# GeigerCounter.net
KiCad netlist of a schematic drawn in EAGLE
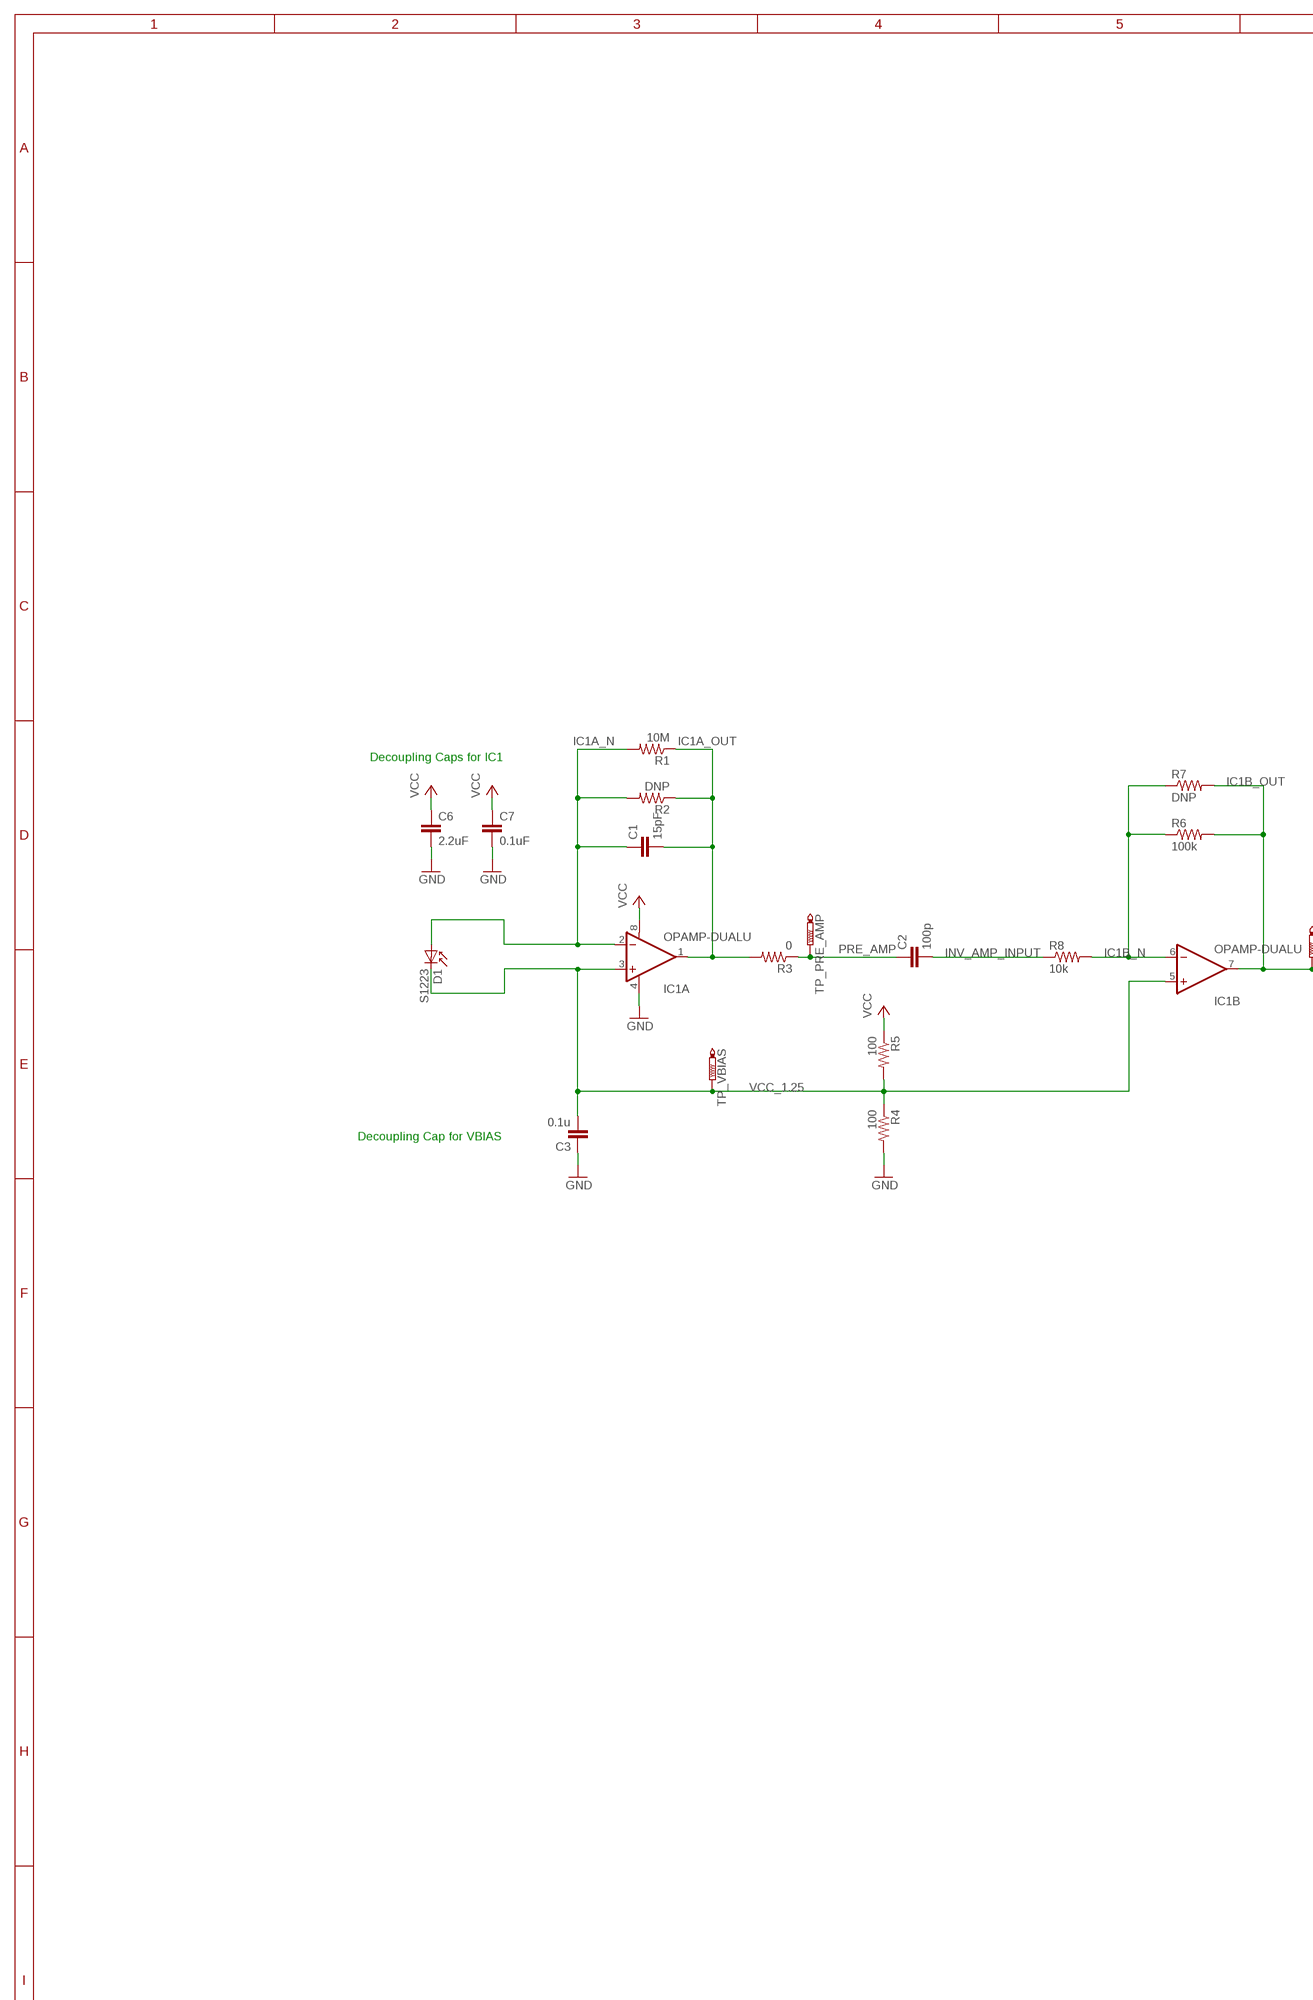
[diagram p0: schematic, sheet 1, part 1 of 2]
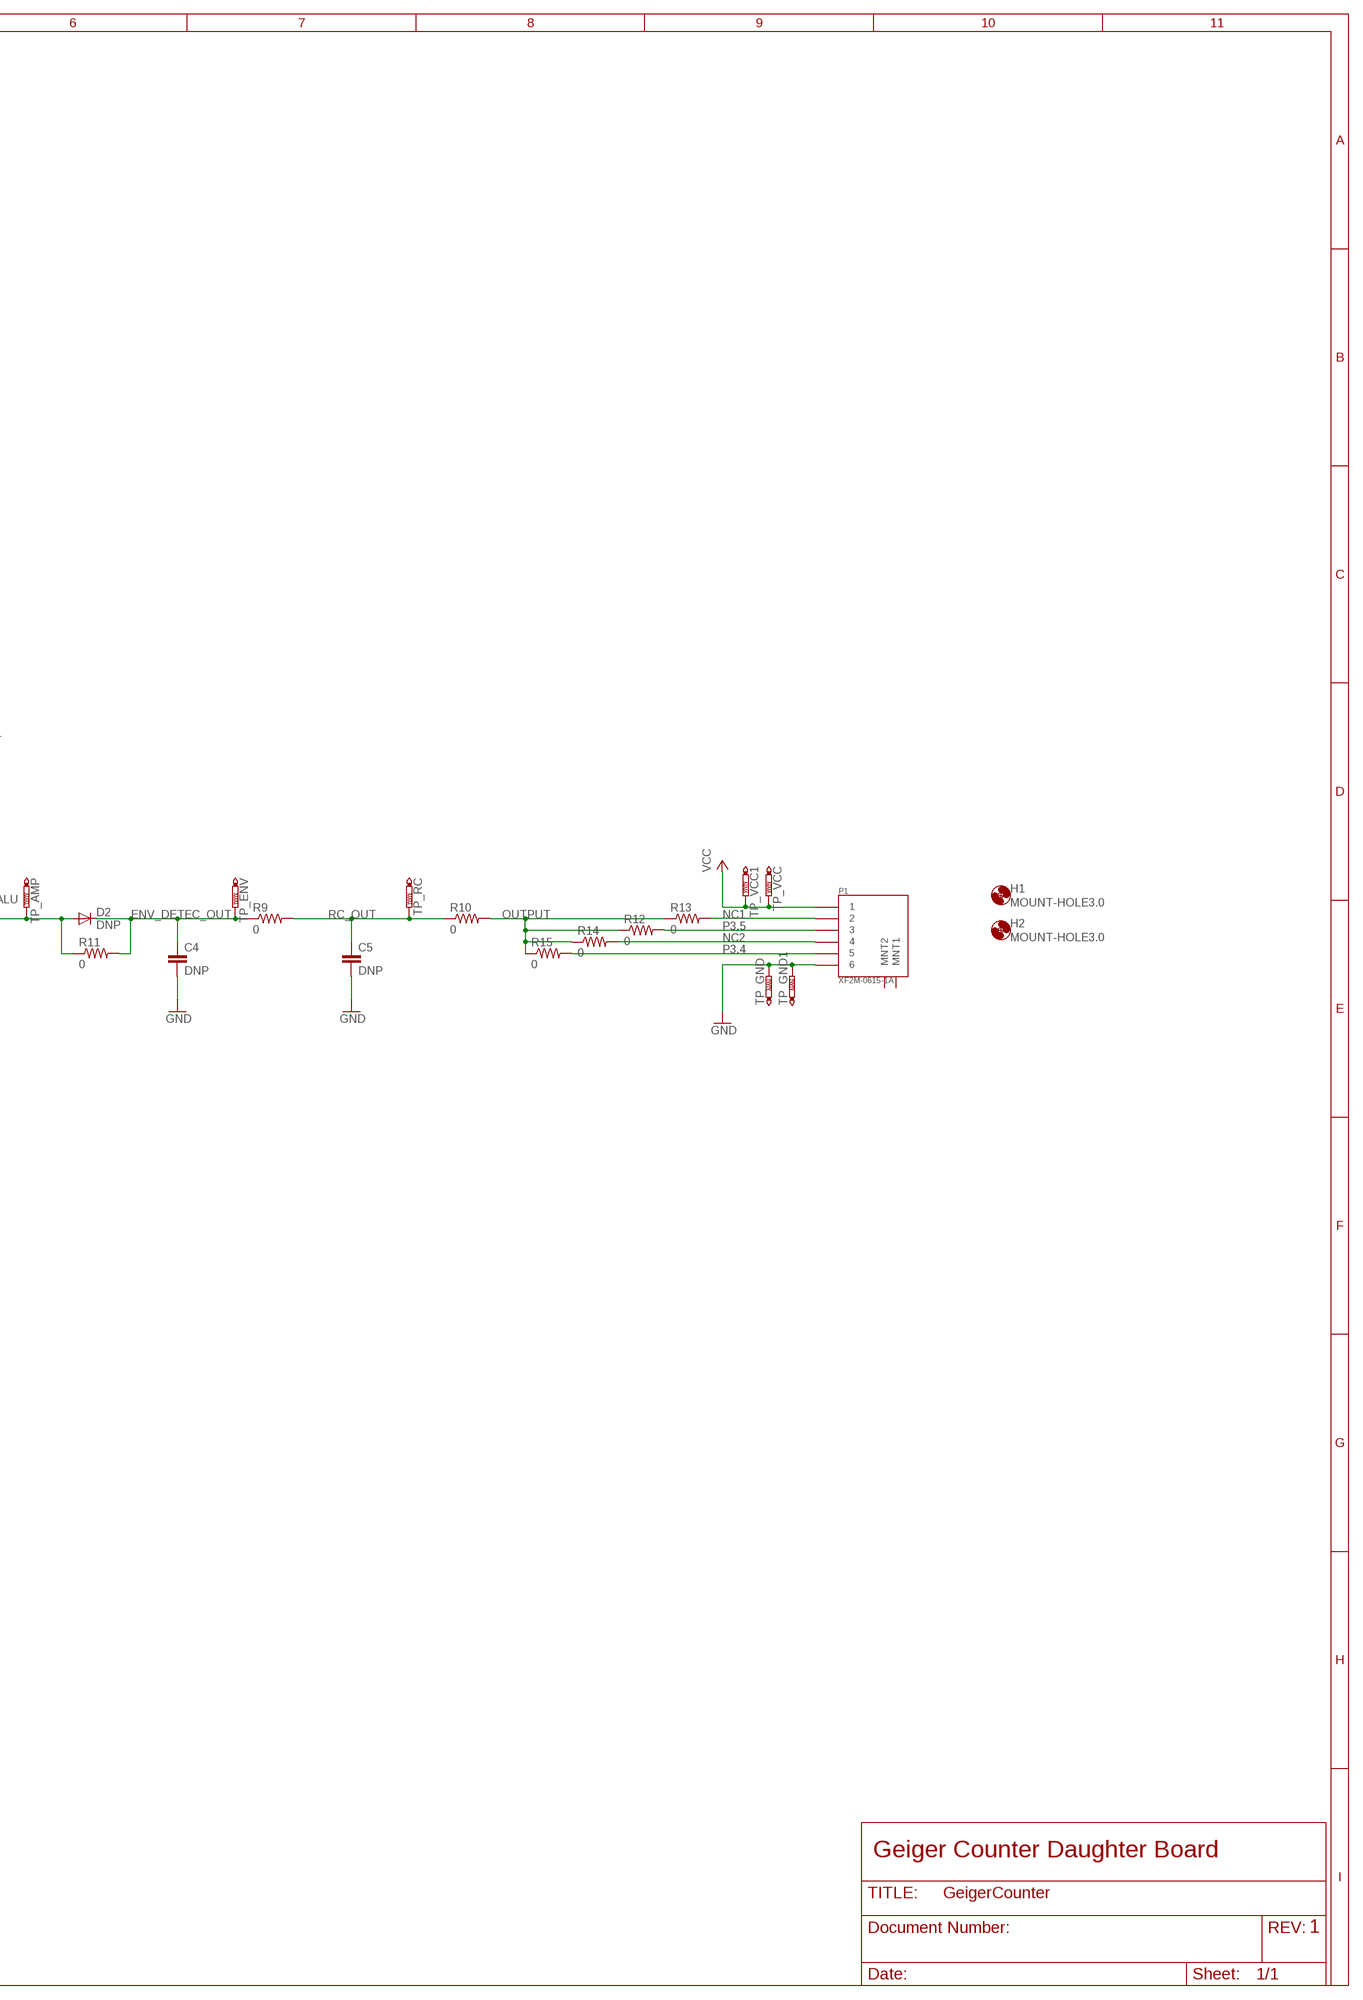
[diagram p1: schematic, sheet 1, part 2 of 2]

(export (version "E")
  (design (tool "Eeschema 10.0.6"))
  (components
    (comp (ref "C1")
      (value "15pF")
      (footprint "eagle-import:0603-CAP")
      (libsource (lib "eagle-import") (part "CAP0603-CAP"))
    )
    (comp (ref "C2")
      (value "100p")
      (footprint "eagle-import:0603-CAP")
      (libsource (lib "eagle-import") (part "CAP0603-CAP"))
    )
    (comp (ref "C3")
      (value "0.1u")
      (footprint "eagle-import:0603-CAP")
      (libsource (lib "eagle-import") (part "CAP0603-CAP"))
    )
    (comp (ref "C4")
      (value "DNP")
      (footprint "eagle-import:0603-CAP")
      (libsource (lib "eagle-import") (part "CAP0603-CAP"))
    )
    (comp (ref "C5")
      (value "DNP")
      (footprint "eagle-import:0603-CAP")
      (libsource (lib "eagle-import") (part "CAP0603-CAP"))
    )
    (comp (ref "C6")
      (value "2.2uF")
      (footprint "eagle-import:0603-CAP")
      (libsource (lib "eagle-import") (part "CAP0603-CAP"))
    )
    (comp (ref "C7")
      (value "0.1uF")
      (footprint "eagle-import:0603-CAP")
      (libsource (lib "eagle-import") (part "CAP0603-CAP"))
    )
    (comp (ref "D1")
      (value "S1223")
      (footprint "eagle-import:DIODE-1N4001")
      (libsource (lib "eagle-import") (part "S1223"))
    )
    (comp (ref "D2")
      (value "DNP")
      (footprint "eagle-import:SOT23-3")
      (libsource (lib "eagle-import") (part "DIODESOT23"))
    )
    (comp (ref "H1")
      (value "MOUNT-HOLE3.0")
      (footprint "eagle-import:3,0")
      (libsource (lib "eagle-import") (part "MOUNT-HOLE3.0"))
    )
    (comp (ref "H2")
      (value "MOUNT-HOLE3.0")
      (footprint "eagle-import:3,0")
      (libsource (lib "eagle-import") (part "MOUNT-HOLE3.0"))
    )
    (comp (ref "IC1")
      (value "OPAMP-DUALU")
      (footprint "eagle-import:SO08")
      (libsource (lib "eagle-import") (part "OPAMP-DUALU"))
    )
    (comp (ref "P1")
      (value "XF2M-0615-1A")
      (footprint "eagle-import:XF2M-0615-1A")
      (libsource (lib "eagle-import") (part "XF2M-0615-1A"))
    )
    (comp (ref "R1")
      (value "10M")
      (footprint "eagle-import:0603-RES")
      (libsource (lib "eagle-import") (part "RESISTOR0603-RES"))
    )
    (comp (ref "R2")
      (value "DNP")
      (footprint "eagle-import:0603-RES")
      (libsource (lib "eagle-import") (part "RESISTOR0603-RES"))
    )
    (comp (ref "R3")
      (value "0")
      (footprint "eagle-import:0603-RES")
      (libsource (lib "eagle-import") (part "RESISTOR0603-RES"))
    )
    (comp (ref "R4")
      (value "100")
      (footprint "eagle-import:0603-RES")
      (libsource (lib "eagle-import") (part "RESISTOR0603-RES"))
    )
    (comp (ref "R5")
      (value "100")
      (footprint "eagle-import:0603-RES")
      (libsource (lib "eagle-import") (part "RESISTOR0603-RES"))
    )
    (comp (ref "R6")
      (value "100k")
      (footprint "eagle-import:0603-RES")
      (libsource (lib "eagle-import") (part "RESISTOR0603-RES"))
    )
    (comp (ref "R7")
      (value "DNP")
      (footprint "eagle-import:0603-RES")
      (libsource (lib "eagle-import") (part "RESISTOR0603-RES"))
    )
    (comp (ref "R8")
      (value "10k")
      (footprint "eagle-import:0603-RES")
      (libsource (lib "eagle-import") (part "RESISTOR0603-RES"))
    )
    (comp (ref "R9")
      (value "0")
      (footprint "eagle-import:0603-RES")
      (libsource (lib "eagle-import") (part "RESISTOR0603-RES"))
    )
    (comp (ref "R10")
      (value "0")
      (footprint "eagle-import:0603-RES")
      (libsource (lib "eagle-import") (part "RESISTOR0603-RES"))
    )
    (comp (ref "R11")
      (value "0")
      (footprint "eagle-import:0603-RES")
      (libsource (lib "eagle-import") (part "RESISTOR0603-RES"))
    )
    (comp (ref "R12")
      (value "0")
      (footprint "eagle-import:0603-RES")
      (libsource (lib "eagle-import") (part "RESISTOR0603-RES"))
    )
    (comp (ref "R13")
      (value "0")
      (footprint "eagle-import:0603-RES")
      (libsource (lib "eagle-import") (part "RESISTOR0603-RES"))
    )
    (comp (ref "R14")
      (value "0")
      (footprint "eagle-import:0603-RES")
      (libsource (lib "eagle-import") (part "RESISTOR0603-RES"))
    )
    (comp (ref "R15")
      (value "0")
      (footprint "eagle-import:0603-RES")
      (libsource (lib "eagle-import") (part "RESISTOR0603-RES"))
    )
    (comp (ref "TP_AMP")
      (value "PTR1PAD1-20")
      (footprint "eagle-import:P1-20")
      (libsource (lib "eagle-import") (part "PTR1PAD1-20"))
    )
    (comp (ref "TP_ENV")
      (value "PTR1PAD1-20")
      (footprint "eagle-import:P1-20")
      (libsource (lib "eagle-import") (part "PTR1PAD1-20"))
    )
    (comp (ref "TP_GND")
      (value "PTR1PAD1-20")
      (footprint "eagle-import:P1-20")
      (libsource (lib "eagle-import") (part "PTR1PAD1-20"))
    )
    (comp (ref "TP_GND1")
      (value "PTR1PAD1-20")
      (footprint "eagle-import:P1-20")
      (libsource (lib "eagle-import") (part "PTR1PAD1-20"))
    )
    (comp (ref "TP_PRE_AMP")
      (value "PTR1PAD1-20")
      (footprint "eagle-import:P1-20")
      (libsource (lib "eagle-import") (part "PTR1PAD1-20"))
    )
    (comp (ref "TP_RC")
      (value "PTR1PAD1-20")
      (footprint "eagle-import:P1-20")
      (libsource (lib "eagle-import") (part "PTR1PAD1-20"))
    )
    (comp (ref "TP_VBIAS")
      (value "PTR1PAD1-20")
      (footprint "eagle-import:P1-20")
      (libsource (lib "eagle-import") (part "PTR1PAD1-20"))
    )
    (comp (ref "TP_VCC")
      (value "PTR1PAD1-20")
      (footprint "eagle-import:P1-20")
      (libsource (lib "eagle-import") (part "PTR1PAD1-20"))
    )
    (comp (ref "TP_VCC1")
      (value "PTR1PAD1-20")
      (footprint "eagle-import:P1-20")
      (libsource (lib "eagle-import") (part "PTR1PAD1-20"))
    )
  )
  (nets
    (net (code "1") (name "/ENV_DETEC_OUT") (class "Default")
      (node (ref "C4") (pin "1") (pinfunction "1_1") (pintype "passive"))
      (node (ref "D2") (pin "3") (pinfunction "C_3") (pintype "passive"))
      (node (ref "R11") (pin "2") (pinfunction "2_2") (pintype "passive"))
      (node (ref "R9") (pin "1") (pinfunction "1_1") (pintype "passive"))
      (node (ref "TP_ENV") (pin "TP") (pinfunction "TP_TP") (pintype "input"))
    )
    (net (code "2") (name "/IC1A_N") (class "Default")
      (node (ref "C1") (pin "1") (pinfunction "1_1") (pintype "passive"))
      (node (ref "D1") (pin "A") (pinfunction "A_A") (pintype "passive"))
      (node (ref "IC1") (pin "2") (pinfunction "-IN_2") (pintype "input"))
      (node (ref "R1") (pin "2") (pinfunction "2_2") (pintype "passive"))
      (node (ref "R2") (pin "2") (pinfunction "2_2") (pintype "passive"))
    )
    (net (code "3") (name "/IC1A_OUT") (class "Default")
      (node (ref "C1") (pin "2") (pinfunction "2_2") (pintype "passive"))
      (node (ref "IC1") (pin "1") (pinfunction "OUT_1") (pintype "output"))
      (node (ref "R1") (pin "1") (pinfunction "1_1") (pintype "passive"))
      (node (ref "R2") (pin "1") (pinfunction "1_1") (pintype "passive"))
      (node (ref "R3") (pin "2") (pinfunction "2_2") (pintype "passive"))
    )
    (net (code "4") (name "/IC1B_N") (class "Default")
      (node (ref "IC1") (pin "6") (pinfunction "-IN_6") (pintype "input"))
      (node (ref "R6") (pin "1") (pinfunction "1_1") (pintype "passive"))
      (node (ref "R7") (pin "1") (pinfunction "1_1") (pintype "passive"))
      (node (ref "R8") (pin "2") (pinfunction "2_2") (pintype "passive"))
    )
    (net (code "5") (name "/IC1B_OUT") (class "Default")
      (node (ref "D2") (pin "1") (pinfunction "A_1") (pintype "passive"))
      (node (ref "IC1") (pin "7") (pinfunction "OUT_7") (pintype "output"))
      (node (ref "R11") (pin "1") (pinfunction "1_1") (pintype "passive"))
      (node (ref "R6") (pin "2") (pinfunction "2_2") (pintype "passive"))
      (node (ref "R7") (pin "2") (pinfunction "2_2") (pintype "passive"))
      (node (ref "TP_AMP") (pin "TP") (pinfunction "TP_TP") (pintype "input"))
    )
    (net (code "6") (name "/INV_AMP_INPUT") (class "Default")
      (node (ref "C2") (pin "2") (pinfunction "2_2") (pintype "passive"))
      (node (ref "R8") (pin "1") (pinfunction "1_1") (pintype "passive"))
    )
    (net (code "7") (name "/NC1") (class "Default")
      (node (ref "P1") (pin "2") (pinfunction "2_2") (pintype "bidirectional"))
      (node (ref "R13") (pin "2") (pinfunction "2_2") (pintype "passive"))
    )
    (net (code "8") (name "/NC2") (class "Default")
      (node (ref "P1") (pin "4") (pinfunction "4_4") (pintype "bidirectional"))
      (node (ref "R14") (pin "2") (pinfunction "2_2") (pintype "passive"))
    )
    (net (code "9") (name "/OUTPUT") (class "Default")
      (node (ref "R10") (pin "2") (pinfunction "2_2") (pintype "passive"))
      (node (ref "R12") (pin "1") (pinfunction "1_1") (pintype "passive"))
      (node (ref "R13") (pin "1") (pinfunction "1_1") (pintype "passive"))
      (node (ref "R14") (pin "1") (pinfunction "1_1") (pintype "passive"))
      (node (ref "R15") (pin "1") (pinfunction "1_1") (pintype "passive"))
    )
    (net (code "10") (name "/P3.4") (class "Default")
      (node (ref "P1") (pin "5") (pinfunction "5_5") (pintype "bidirectional"))
      (node (ref "R15") (pin "2") (pinfunction "2_2") (pintype "passive"))
    )
    (net (code "11") (name "/P3.5") (class "Default")
      (node (ref "P1") (pin "3") (pinfunction "3_3") (pintype "bidirectional"))
      (node (ref "R12") (pin "2") (pinfunction "2_2") (pintype "passive"))
    )
    (net (code "12") (name "/PRE_AMP") (class "Default")
      (node (ref "C2") (pin "1") (pinfunction "1_1") (pintype "passive"))
      (node (ref "R3") (pin "1") (pinfunction "1_1") (pintype "passive"))
      (node (ref "TP_PRE_AMP") (pin "TP") (pinfunction "TP_TP") (pintype "input"))
    )
    (net (code "13") (name "/RC_OUT") (class "Default")
      (node (ref "C5") (pin "1") (pinfunction "1_1") (pintype "passive"))
      (node (ref "R10") (pin "1") (pinfunction "1_1") (pintype "passive"))
      (node (ref "R9") (pin "2") (pinfunction "2_2") (pintype "passive"))
      (node (ref "TP_RC") (pin "TP") (pinfunction "TP_TP") (pintype "input"))
    )
    (net (code "14") (name "/VCC_1.25") (class "Default")
      (node (ref "C3") (pin "2") (pinfunction "2_2") (pintype "passive"))
      (node (ref "D1") (pin "C") (pinfunction "C_C") (pintype "passive"))
      (node (ref "IC1") (pin "3") (pinfunction "+IN_3") (pintype "input"))
      (node (ref "IC1") (pin "5") (pinfunction "+IN_5") (pintype "input"))
      (node (ref "R4") (pin "1") (pinfunction "1_1") (pintype "passive"))
      (node (ref "R5") (pin "2") (pinfunction "2_2") (pintype "passive"))
      (node (ref "TP_VBIAS") (pin "TP") (pinfunction "TP_TP") (pintype "input"))
    )
    (net (code "15") (name "GND") (class "Default")
      (node (ref "C3") (pin "1") (pinfunction "1_1") (pintype "passive"))
      (node (ref "C4") (pin "2") (pinfunction "2_2") (pintype "passive"))
      (node (ref "C5") (pin "2") (pinfunction "2_2") (pintype "passive"))
      (node (ref "C6") (pin "2") (pinfunction "2_2") (pintype "passive"))
      (node (ref "C7") (pin "2") (pinfunction "2_2") (pintype "passive"))
      (node (ref "IC1") (pin "4") (pinfunction "V-_4") (pintype "power_in"))
      (node (ref "P1") (pin "6") (pinfunction "6_6") (pintype "bidirectional"))
      (node (ref "R4") (pin "2") (pinfunction "2_2") (pintype "passive"))
      (node (ref "TP_GND") (pin "TP") (pinfunction "TP_TP") (pintype "input"))
      (node (ref "TP_GND1") (pin "TP") (pinfunction "TP_TP") (pintype "input"))
    )
    (net (code "16") (name "VCC") (class "Default")
      (node (ref "C6") (pin "1") (pinfunction "1_1") (pintype "passive"))
      (node (ref "C7") (pin "1") (pinfunction "1_1") (pintype "passive"))
      (node (ref "IC1") (pin "8") (pinfunction "V+_8") (pintype "power_in"))
      (node (ref "P1") (pin "1") (pinfunction "1_1") (pintype "bidirectional"))
      (node (ref "R5") (pin "1") (pinfunction "1_1") (pintype "passive"))
      (node (ref "TP_VCC") (pin "TP") (pinfunction "TP_TP") (pintype "input"))
      (node (ref "TP_VCC1") (pin "TP") (pinfunction "TP_TP") (pintype "input"))
    )
    (net (code "17") (name "unconnected-(P1-MNT1-PadP$7)") (class "Default")
      (node (ref "P1") (pin "P$7") (pinfunction "MNT1_P$7") (pintype "no_connect"))
    )
    (net (code "18") (name "unconnected-(P1-MNT2-PadP$8)") (class "Default")
      (node (ref "P1") (pin "P$8") (pinfunction "MNT2_P$8") (pintype "no_connect"))
    )
  )
)
